# Gate_Driver.net
KiCad netlist of a schematic drawn in Altium Designer
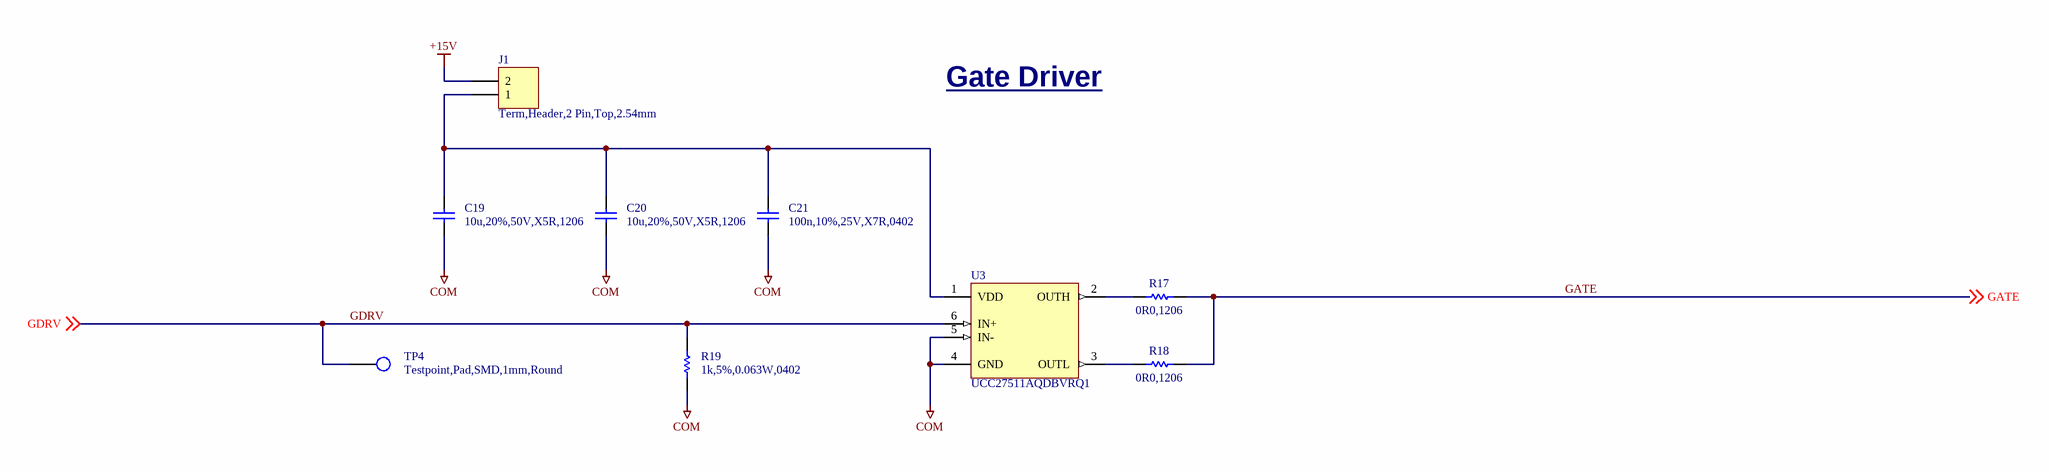
[diagram p0: Gate Driver.SchDoc]

(export (version "E")
  (design (tool "Eeschema 10.0.6"))
  (components
    (comp (ref "C19")
      (value "10u,20%,50V,X5R,1206")
      (footprint "CAPC3216X16N")
      (description "10ï¿½F ï¿½20% 50V Ceramic Capacitor X5R 1206 (3216 Metric)")
      (fields
        (field (name "MANUFACTURER 1 PART NUMBER") "CL31A106MBHNNNE")
        (field (name "VENDOR 1 PART NUMBER") "1276-6736-1-ND")
        (field (name "CREATEDBY") "Judd Foster")
      )
      (libsource (lib "Component Library") (part "CAP,Cer,10uF,50VDC,X5R,1206"))
    )
    (comp (ref "C20")
      (value "10u,20%,50V,X5R,1206")
      (footprint "CAPC3216X16N")
      (description "10ï¿½F ï¿½20% 50V Ceramic Capacitor X5R 1206 (3216 Metric)")
      (fields
        (field (name "MANUFACTURER 1 PART NUMBER") "CL31A106MBHNNNE")
        (field (name "VENDOR 1 PART NUMBER") "1276-6736-1-ND")
        (field (name "CREATEDBY") "Judd Foster")
      )
      (libsource (lib "Component Library") (part "CAP,Cer,10uF,50VDC,X5R,1206"))
    )
    (comp (ref "C21")
      (value "100n,10%,25V,X7R,0402")
      (footprint "CAPC1005X06N")
      (description "0.1ï¿½F ï¿½10% 25V Ceramic Capacitor X7R 0402 (1005 Metric)")
      (fields
        (field (name "MANUFACTURER 1 PART NUMBER") "GRM155R71E104KE14J")
        (field (name "VENDOR 1 PART NUMBER") "490-14603-1-ND")
        (field (name "CREATEDBY") "Judd Foster")
      )
      (libsource (lib "Component Library") (part "CAP,Cer,100nF,10%,25V,X7R,0402"))
    )
    (comp (ref "J1")
      (value "Term,Header,2 Pin,Top,2.54mm")
      (footprint "WURTH_61300211121")
      (description "Connector Header Through Hole 2 position 0.100\" (2.54mm)")
      (fields
        (field (name "MANUFACTURER 1 PART NUMBER") "61300211121")
        (field (name "VENDOR 1 PART NUMBER") "732-5315-ND")
        (field (name "CREATEDBY") "Judd Foster")
      )
      (libsource (lib "Component Library") (part "Term,Header,2 Pin,Top,2.54mm"))
    )
    (comp (ref "R17")
      (value "0R0,1206")
      (footprint "RESC3216X06N")
      (description "0 Ohms Jumper Chip Resistor 1206 (3216 Metric) Automotive AEC-Q200 Thick Film")
      (fields
        (field (name "MANUFACTURER 1 PART NUMBER") "RMCF1206ZT0R00")
        (field (name "VENDOR 1 PART NUMBER") "RMCF1206ZT0R00CT-ND")
        (field (name "CREATEDBY") "Judd Foster")
      )
      (libsource (lib "Component Library") (part "RES,0R0,1206"))
    )
    (comp (ref "R18")
      (value "0R0,1206")
      (footprint "RESC3216X06N")
      (description "0 Ohms Jumper Chip Resistor 1206 (3216 Metric) Automotive AEC-Q200 Thick Film")
      (fields
        (field (name "MANUFACTURER 1 PART NUMBER") "RMCF1206ZT0R00")
        (field (name "VENDOR 1 PART NUMBER") "RMCF1206ZT0R00CT-ND")
        (field (name "CREATEDBY") "Judd Foster")
      )
      (libsource (lib "Component Library") (part "RES,0R0,1206"))
    )
    (comp (ref "R19")
      (value "1k,5%,0.063W,0402")
      (footprint "RESC1005X04N")
      (description "1 kOhms ï¿½5% 0.063W, 1/16W Chip Resistor 0402 (1005 Metric) Automotive AEC-Q200 Thick Film")
      (fields
        (field (name "MANUFACTURER 1 PART NUMBER") "RMCF0402JT1K00")
        (field (name "VENDOR 1 PART NUMBER") "RMCF0402JT1K00CT-ND")
        (field (name "CREATEDBY") "Judd Foster")
      )
      (libsource (lib "Component Library") (part "RES,1k,5%,0.063W,0402"))
    )
    (comp (ref "TP4")
      (value "Testpoint,Pad,SMD,1mm,Round")
      (footprint "TP100")
      (description "PCB Testpoint 1mm Round")
      (fields (field (name "CREATEDBY") "Judd Foster"))
      (libsource (lib "Component Library") (part "Testpoint,Pad,SMD"))
    )
    (comp (ref "U3")
      (value "UCC27511AQDBVRQ1")
      (footprint "SOTFL95P260X145-6")
      (description "Gate Drivers Sngl-Ch high-Spd Low-Side Gate Driver")
      (fields
        (field (name "VENDOR 1 PART NUMBER") "595-UCC27511AQDBVRQ1")
        (field (name "CREATEDBY") "Judd Foster")
      )
      (libsource (lib "Component Library") (part "UCC27511AQDBVRQ1"))
    )
  )
  (nets
    (net (code "1") (name "+15V") (class "Default")
      (node (ref "J1") (pin "2") (pinfunction "2_2") (pintype "passive"))
    )
    (net (code "2") (name "COM") (class "Default")
      (node (ref "C19") (pin "1") (pinfunction "1_1") (pintype "passive"))
      (node (ref "C20") (pin "1") (pinfunction "1_1") (pintype "passive"))
      (node (ref "C21") (pin "1") (pinfunction "1_1") (pintype "passive"))
      (node (ref "R19") (pin "1") (pinfunction "1_1") (pintype "passive"))
      (node (ref "U3") (pin "4") (pinfunction "GND_4") (pintype "power_in"))
      (node (ref "U3") (pin "5") (pinfunction "IN-_5") (pintype "input"))
    )
    (net (code "3") (name "GATE") (class "Default")
      (node (ref "R17") (pin "2") (pinfunction "2_2") (pintype "passive"))
      (node (ref "R18") (pin "2") (pinfunction "2_2") (pintype "passive"))
    )
    (net (code "4") (name "GDRV") (class "Default")
      (node (ref "R19") (pin "2") (pinfunction "2_2") (pintype "passive"))
      (node (ref "TP4") (pin "1") (pinfunction "TP_1") (pintype "passive"))
      (node (ref "U3") (pin "6") (pinfunction "IN+_6") (pintype "input"))
    )
    (net (code "5") (name "Net-(U3-OUTH)") (class "Default")
      (node (ref "R17") (pin "1") (pinfunction "1_1") (pintype "passive"))
      (node (ref "U3") (pin "2") (pinfunction "OUTH_2") (pintype "output"))
    )
    (net (code "6") (name "Net-(U3-OUTL)") (class "Default")
      (node (ref "R18") (pin "1") (pinfunction "1_1") (pintype "passive"))
      (node (ref "U3") (pin "3") (pinfunction "OUTL_3") (pintype "output"))
    )
    (net (code "7") (name "Net-(U3-VDD)") (class "Default")
      (node (ref "C19") (pin "2") (pinfunction "2_2") (pintype "passive"))
      (node (ref "C20") (pin "2") (pinfunction "2_2") (pintype "passive"))
      (node (ref "C21") (pin "2") (pinfunction "2_2") (pintype "passive"))
      (node (ref "J1") (pin "1") (pinfunction "1_1") (pintype "passive"))
      (node (ref "U3") (pin "1") (pinfunction "VDD_1") (pintype "power_in"))
    )
  )
)
